# design.net
KiCad netlist of a schematic drawn in EasyEDA Pro
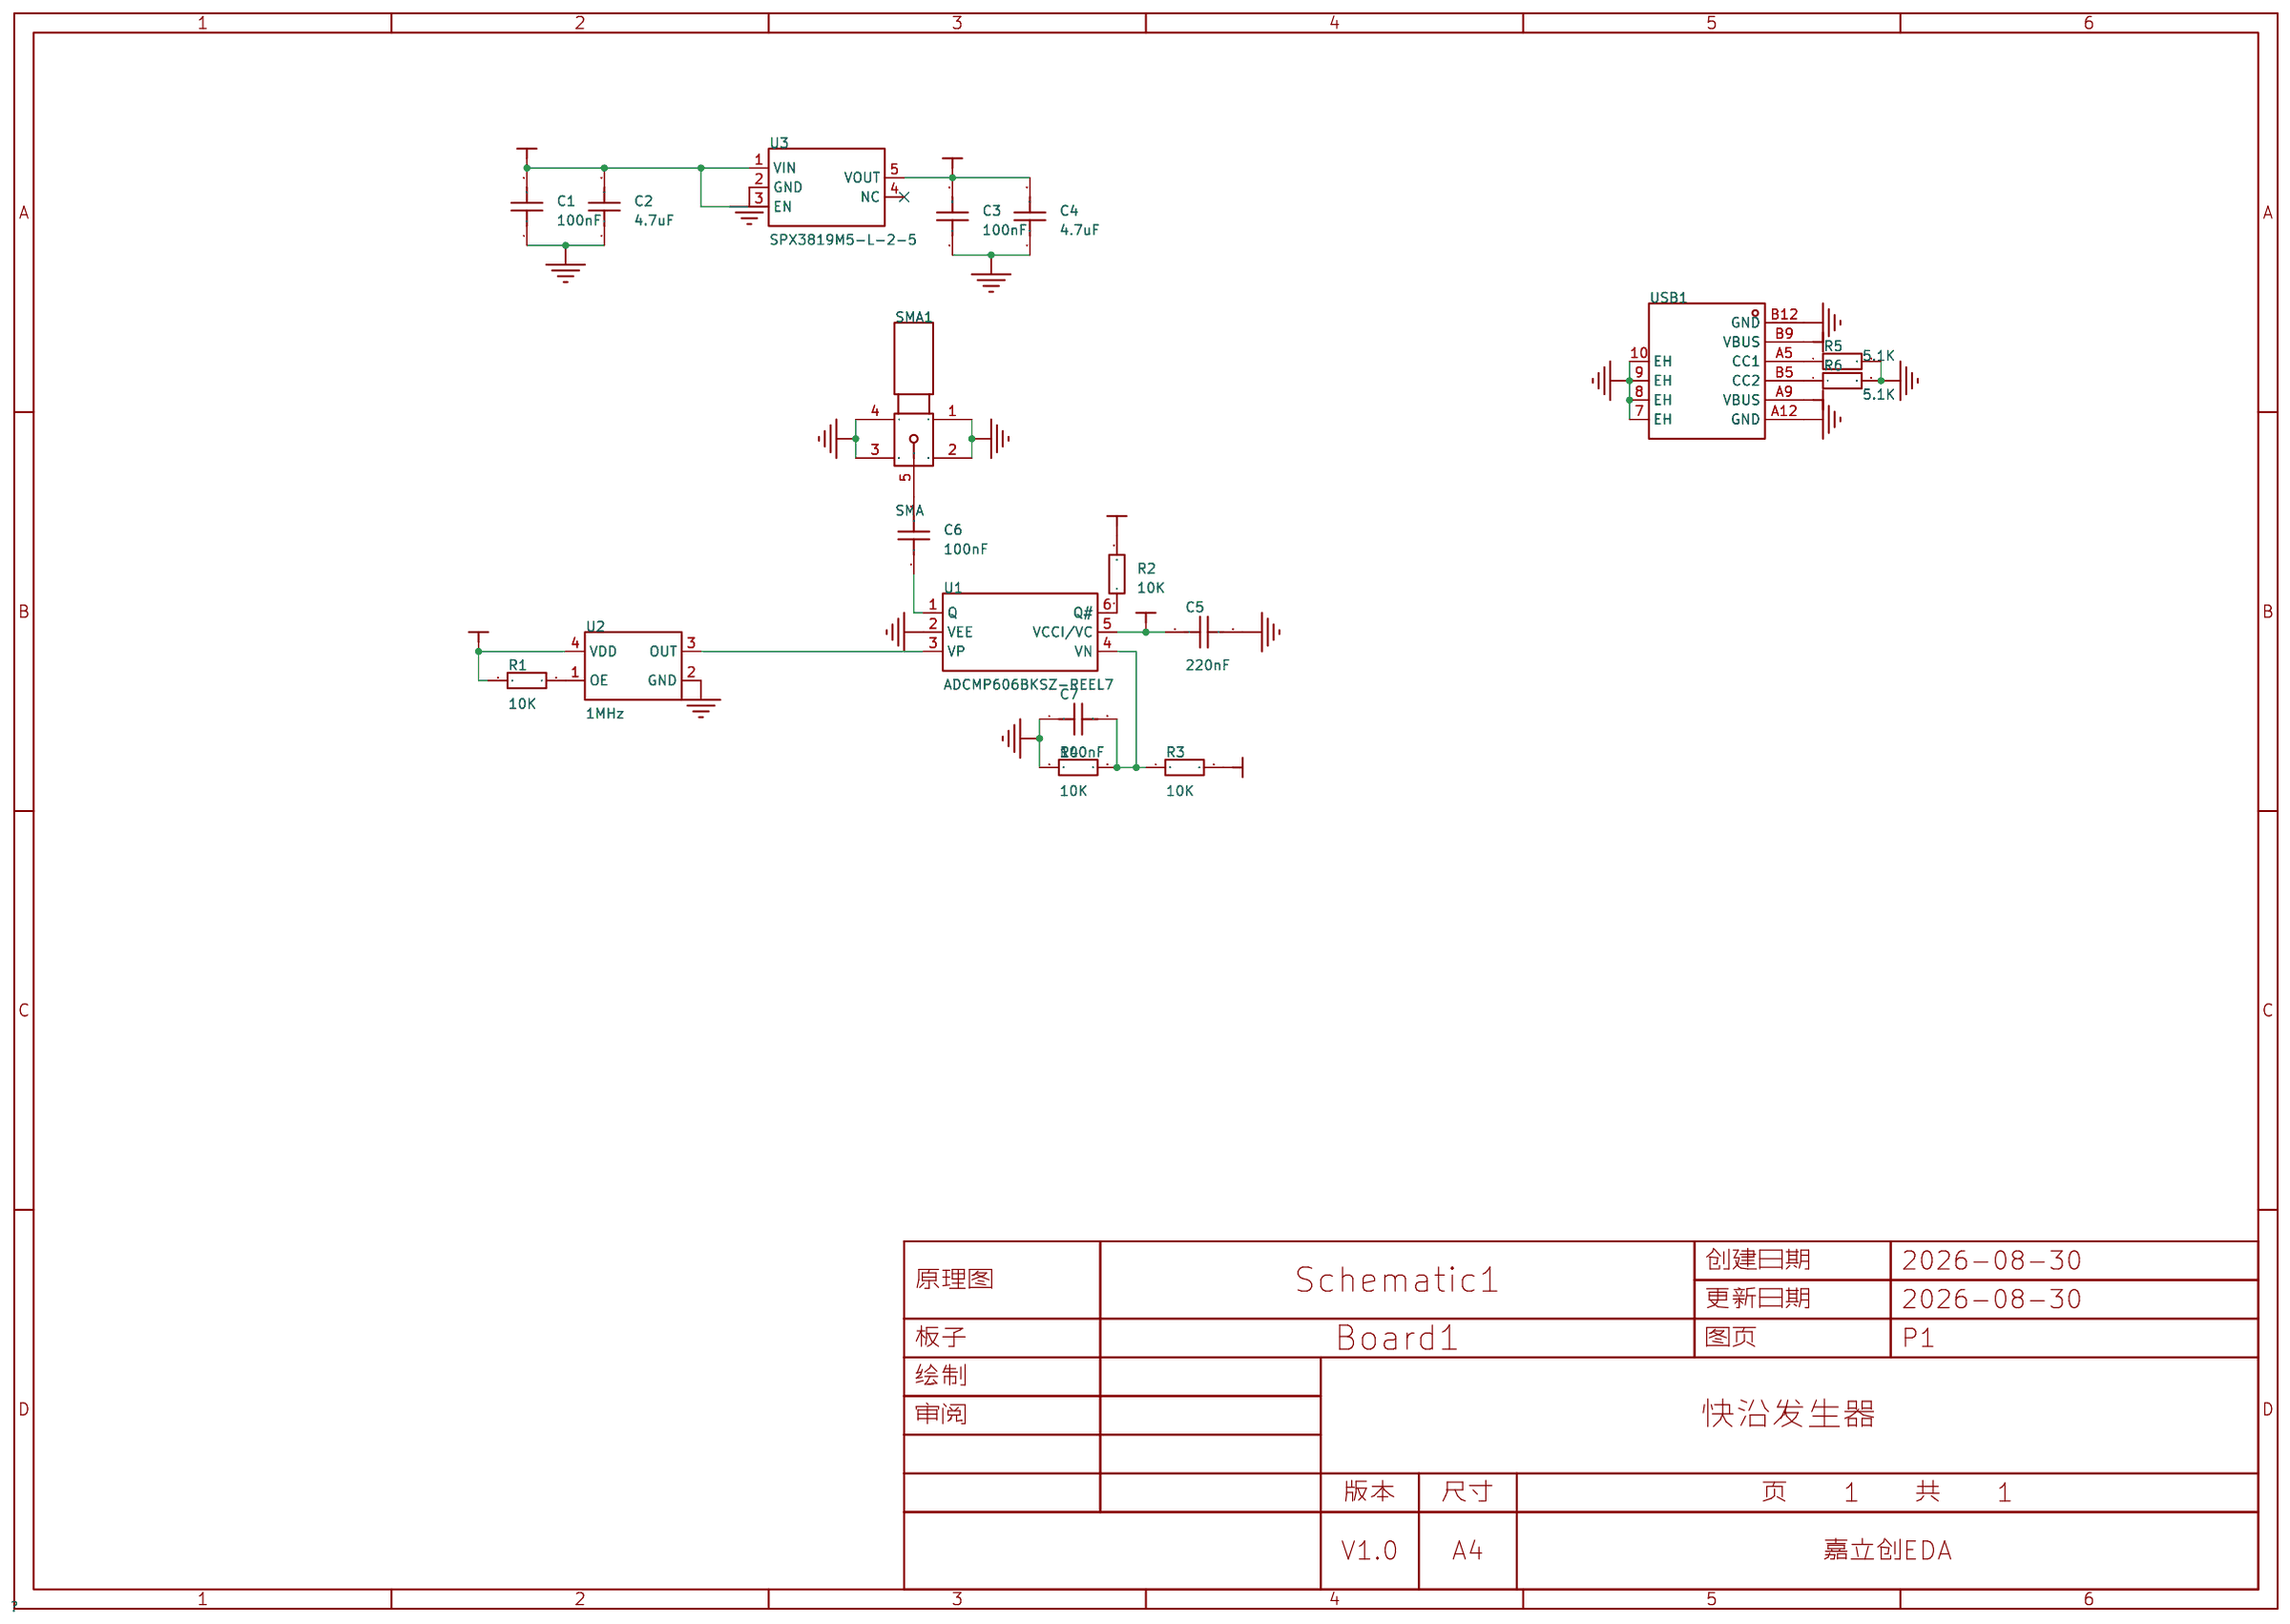
[diagram p0: schematic sheet]

(export (version "E")
  (design (tool "Eeschema 10.0.6"))
  (components
    (comp (ref "C1")
      (value "100nF")
      (footprint "easyedapro:C0805")
      (libsource (lib "easyedapro") (part "Capacitance"))
    )
    (comp (ref "C2")
      (value "4.7uF")
      (footprint "easyedapro:C0805")
      (libsource (lib "easyedapro") (part "Capacitance"))
    )
    (comp (ref "C3")
      (value "100nF")
      (footprint "easyedapro:C0805")
      (libsource (lib "easyedapro") (part "Capacitance"))
    )
    (comp (ref "C4")
      (value "4.7uF")
      (footprint "easyedapro:C0805")
      (libsource (lib "easyedapro") (part "Capacitance"))
    )
    (comp (ref "C5")
      (value "220nF")
      (footprint "easyedapro:C0805")
      (libsource (lib "easyedapro") (part "Capacitance"))
    )
    (comp (ref "C6")
      (value "100nF")
      (footprint "easyedapro:C0805")
      (libsource (lib "easyedapro") (part "Capacitance"))
    )
    (comp (ref "C7")
      (value "100nF")
      (footprint "easyedapro:C0805")
      (libsource (lib "easyedapro") (part "Capacitance"))
    )
    (comp (ref "R1") (value "10K") (footprint "easyedapro:R0603") (libsource (lib "easyedapro") (part "电阻")))
    (comp (ref "R2") (value "10K") (footprint "easyedapro:R0603") (libsource (lib "easyedapro") (part "电阻")))
    (comp (ref "R3") (value "10K") (footprint "easyedapro:R0603") (libsource (lib "easyedapro") (part "电阻")))
    (comp (ref "R4") (value "10K") (footprint "easyedapro:R0603") (libsource (lib "easyedapro") (part "电阻")))
    (comp (ref "R5") (value "5.1K") (footprint "easyedapro:R0603") (libsource (lib "easyedapro") (part "电阻")))
    (comp (ref "R6") (value "5.1K") (footprint "easyedapro:R0603") (libsource (lib "easyedapro") (part "电阻")))
    (comp (ref "SMA1")
      (value "SMA")
      (footprint "easyedapro:SMA-SMD_BWSMA-KE-P001")
      (libsource (lib "easyedapro") (part "SMA_C9900018296"))
    )
    (comp (ref "U1")
      (value "ADCMP606BKSZ-REEL7")
      (footprint "easyedapro:SC-70-6_L2.0-W1.3-P0.65-LS2.1-BR")
      (fields (field (name "Manufacturer") "ADI(亚德诺)"))
      (libsource (lib "easyedapro") (part "ADCMP606BKSZ-REEL7"))
    )
    (comp (ref "U2")
      (value "1MHz")
      (footprint "easyedapro:OSC-SMD_4P-L3.2-W2.5-BL")
      (fields
        (field (name "Manufacturer Part") "SX3M1.000M20F30TNN")
        (field (name "Manufacturer") "SCTF(星通时频)")
      )
      (libsource (lib "easyedapro") (part "SX3M1.000M20F30TNN"))
    )
    (comp (ref "U3")
      (value "SPX3819M5-L-2-5")
      (footprint "easyedapro:SOT-23-5_L2.9-W1.6-P0.95-LS2.8-BR")
      (fields (field (name "Manufacturer") "TECH PUBLIC(台舟)"))
      (libsource (lib "easyedapro") (part "SPX3819M5-L-2-5_C23380893"))
    )
    (comp (ref "USB1")
      (value "~")
      (footprint "easyedapro:USB_ TYPE-C-6P")
      (libsource (lib "easyedapro") (part "USB_ TYPE-C-6P"))
    )
  )
  (nets
    (net (code "1") (name "3V3") (class "Default")
      (node (ref "C3") (pin "2") (pinfunction "2_2") (pintype "input"))
      (node (ref "C4") (pin "2") (pinfunction "2_2") (pintype "input"))
      (node (ref "C5") (pin "1") (pinfunction "1_1") (pintype "input"))
      (node (ref "R1") (pin "1") (pinfunction "1_1") (pintype "input"))
      (node (ref "R2") (pin "2") (pinfunction "2_2") (pintype "input"))
      (node (ref "R3") (pin "2") (pinfunction "2_2") (pintype "input"))
      (node (ref "U1") (pin "5") (pinfunction "VCCI/VC_5") (pintype "unspecified"))
      (node (ref "U2") (pin "4") (pinfunction "VDD_4") (pintype "unspecified"))
      (node (ref "U3") (pin "5") (pinfunction "VOUT_5") (pintype "unspecified"))
    )
    (net (code "2") (name "GND") (class "Default")
      (node (ref "C1") (pin "1") (pinfunction "1_1") (pintype "input"))
      (node (ref "C2") (pin "1") (pinfunction "1_1") (pintype "input"))
      (node (ref "C3") (pin "1") (pinfunction "1_1") (pintype "input"))
      (node (ref "C4") (pin "1") (pinfunction "1_1") (pintype "input"))
      (node (ref "C5") (pin "2") (pinfunction "2_2") (pintype "input"))
      (node (ref "C7") (pin "1") (pinfunction "1_1") (pintype "input"))
      (node (ref "R4") (pin "1") (pinfunction "1_1") (pintype "input"))
      (node (ref "R5") (pin "2") (pinfunction "2_2") (pintype "input"))
      (node (ref "R6") (pin "2") (pinfunction "2_2") (pintype "input"))
      (node (ref "SMA1") (pin "1") (pinfunction "1_1") (pintype "unspecified"))
      (node (ref "SMA1") (pin "2") (pinfunction "2_2") (pintype "unspecified"))
      (node (ref "SMA1") (pin "3") (pinfunction "3_3") (pintype "unspecified"))
      (node (ref "SMA1") (pin "4") (pinfunction "4_4") (pintype "unspecified"))
      (node (ref "U1") (pin "2") (pinfunction "VEE_2") (pintype "unspecified"))
      (node (ref "U2") (pin "2") (pinfunction "GND_2") (pintype "unspecified"))
      (node (ref "U3") (pin "2") (pinfunction "GND_2") (pintype "unspecified"))
      (node (ref "USB1") (pin "10") (pinfunction "EH_10") (pintype "input"))
      (node (ref "USB1") (pin "7") (pinfunction "EH_7") (pintype "input"))
      (node (ref "USB1") (pin "8") (pinfunction "EH_8") (pintype "input"))
      (node (ref "USB1") (pin "9") (pinfunction "EH_9") (pintype "input"))
      (node (ref "USB1") (pin "A12") (pinfunction "GND_A12") (pintype "input"))
      (node (ref "USB1") (pin "B12") (pinfunction "GND_B12") (pintype "input"))
    )
    (net (code "3") (name "Net-(C6-Pad2)") (class "Default")
      (node (ref "C6") (pin "2") (pinfunction "2_2") (pintype "input"))
      (node (ref "SMA1") (pin "5") (pinfunction "5_5") (pintype "unspecified"))
    )
    (net (code "4") (name "Net-(U1-Q#)") (class "Default")
      (node (ref "R2") (pin "1") (pinfunction "1_1") (pintype "input"))
      (node (ref "U1") (pin "6") (pinfunction "Q#_6") (pintype "unspecified"))
    )
    (net (code "5") (name "Net-(U1-Q)") (class "Default")
      (node (ref "C6") (pin "1") (pinfunction "1_1") (pintype "input"))
      (node (ref "U1") (pin "1") (pinfunction "Q_1") (pintype "unspecified"))
    )
    (net (code "6") (name "Net-(U1-VN)") (class "Default")
      (node (ref "C7") (pin "2") (pinfunction "2_2") (pintype "input"))
      (node (ref "R3") (pin "1") (pinfunction "1_1") (pintype "input"))
      (node (ref "R4") (pin "2") (pinfunction "2_2") (pintype "input"))
      (node (ref "U1") (pin "4") (pinfunction "VN_4") (pintype "unspecified"))
    )
    (net (code "7") (name "Net-(U1-VP)") (class "Default")
      (node (ref "U1") (pin "3") (pinfunction "VP_3") (pintype "unspecified"))
      (node (ref "U2") (pin "3") (pinfunction "OUT_3") (pintype "unspecified"))
    )
    (net (code "8") (name "Net-(U2-OE)") (class "Default")
      (node (ref "R1") (pin "2") (pinfunction "2_2") (pintype "input"))
      (node (ref "U2") (pin "1") (pinfunction "OE_1") (pintype "unspecified"))
    )
    (net (code "9") (name "Net-(USB1-CC1)") (class "Default")
      (node (ref "R5") (pin "1") (pinfunction "1_1") (pintype "input"))
      (node (ref "USB1") (pin "A5") (pinfunction "CC1_A5") (pintype "input"))
    )
    (net (code "10") (name "Net-(USB1-CC2)") (class "Default")
      (node (ref "R6") (pin "1") (pinfunction "1_1") (pintype "input"))
      (node (ref "USB1") (pin "B5") (pinfunction "CC2_B5") (pintype "input"))
    )
    (net (code "11") (name "VCC") (class "Default")
      (node (ref "C1") (pin "2") (pinfunction "2_2") (pintype "input"))
      (node (ref "C2") (pin "2") (pinfunction "2_2") (pintype "input"))
      (node (ref "U3") (pin "1") (pinfunction "VIN_1") (pintype "unspecified"))
      (node (ref "U3") (pin "3") (pinfunction "EN_3") (pintype "unspecified"))
      (node (ref "USB1") (pin "A9") (pinfunction "VBUS_A9") (pintype "input"))
      (node (ref "USB1") (pin "B9") (pinfunction "VBUS_B9") (pintype "input"))
    )
    (net (code "12") (name "unconnected-(U3-NC-Pad4)") (class "Default")
      (node (ref "U3") (pin "4") (pinfunction "NC_4") (pintype "unspecified+no_connect"))
    )
  )
)
